# B.net
KiCad netlist of a schematic drawn in Altium Designer
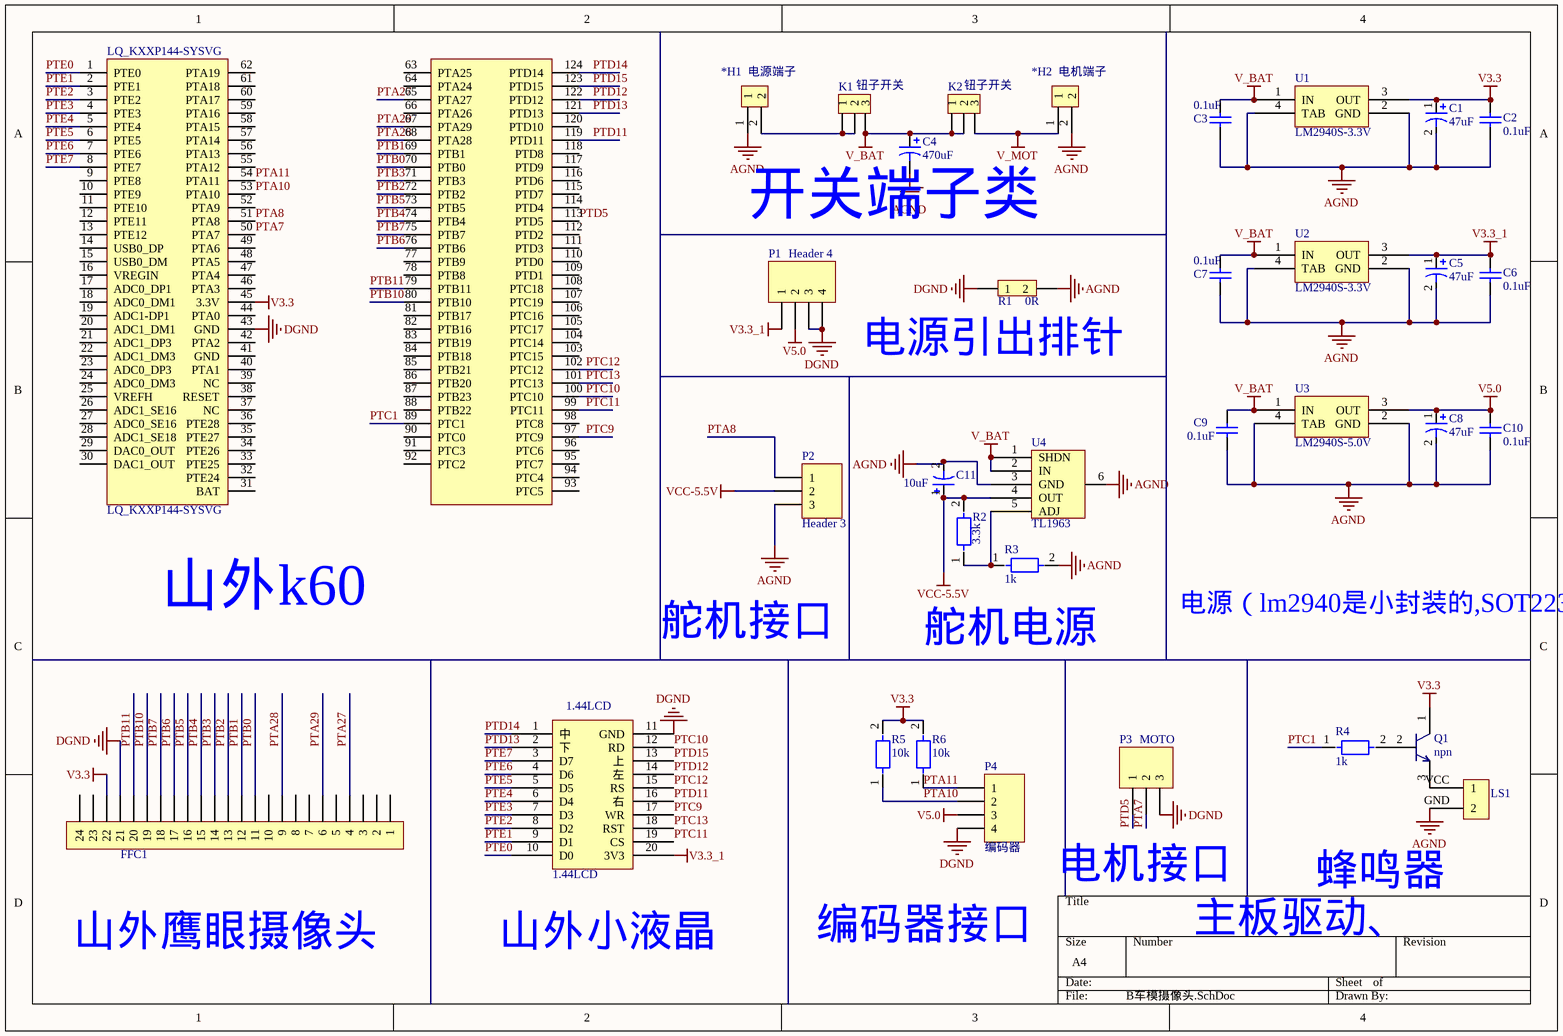
[diagram p0: B车模摄像头.SchDoc]

(export (version "E")
  (design (tool "Eeschema 10.0.6"))
  (components
    (comp (ref "*H1") (value "电源端子") (footprint "端子") (libsource (lib "Integrated_Library") (part "端子5MM")))
    (comp (ref "*H2") (value "电机端子") (footprint "端子") (libsource (lib "Integrated_Library") (part "端子5MM")))
    (comp (ref "1.44LCD")
      (value "1.44LCD")
      (footprint "1.44LCD")
      (libsource (lib "1.44LCD") (part "1.44LCD"))
    )
    (comp (ref "C1") (value "47uF") (footprint "3216") (libsource (lib "MOTOR") (part "CAP-TAN-47uF")))
    (comp (ref "C2") (value "0.1uF") (footprint "0805") (libsource (lib "MOTOR") (part "CAP-0805_1")))
    (comp (ref "C3") (value "0.1uF") (footprint "0805") (libsource (lib "MOTOR") (part "CAP-0805_1")))
    (comp (ref "C4")
      (value "470uF")
      (footprint "470UF")
      (description "Polarized Capacitor (Radial)")
      (fields (field (name "Comment") "Cap Pol1") (field (name "PUBLISHER") "Altium Limited"))
      (libsource (lib "第十届摄像头主板工程") (part "Cap Pol1"))
    )
    (comp (ref "C5") (value "47uF") (footprint "3216") (libsource (lib "MOTOR") (part "CAP-TAN-47uF")))
    (comp (ref "C6") (value "0.1uF") (footprint "0805") (libsource (lib "MOTOR") (part "CAP-0805_1")))
    (comp (ref "C7") (value "0.1uF") (footprint "0805") (libsource (lib "MOTOR") (part "CAP-0805_1")))
    (comp (ref "C8") (value "47uF") (footprint "3216") (libsource (lib "MOTOR") (part "CAP-TAN-47uF")))
    (comp (ref "C9") (value "0.1uF") (footprint "0805") (libsource (lib "MOTOR") (part "CAP-0805_1")))
    (comp (ref "C10") (value "0.1uF") (footprint "0805") (libsource (lib "MOTOR") (part "CAP-0805_1")))
    (comp (ref "C11") (value "10uF") (footprint "3216") (libsource (lib "MOTOR") (part "CAP-TAN-10uF")))
    (comp (ref "FFC1")
      (value "FFC_0.5_24")
      (footprint "摄像头软排")
      (description "FFC")
      (libsource (lib "第十届摄像头主板工程") (part "FFC_0.5_24"))
    )
    (comp (ref "K1")
      (value "钮子开关")
      (footprint "钮子开关")
      (description "钮子开关102")
      (libsource (lib "Integrated_Library") (part "钮子开关"))
    )
    (comp (ref "K2")
      (value "钮子开关")
      (footprint "钮子开关")
      (description "钮子开关102")
      (libsource (lib "Integrated_Library") (part "钮子开关"))
    )
    (comp (ref "LQ_KXXP144-SYSVG")
      (value "LQ_KXXP144-SYSVG")
      (footprint "LQ_KXXP144-SYSVG")
      (libsource (lib "LQ_KXXP144-SYSVGSCH") (part "LQ_KXXP144-SYSVG"))
    )
    (comp (ref "LS1")
      (value "0905小型蜂鸣器")
      (footprint "0905小型蜂鸣器")
      (description "0905小蜂鸣器")
      (libsource (lib "Integrated_Library") (part "0905小型蜂鸣器"))
    )
    (comp (ref "P1")
      (value "Header 4")
      (footprint "HDR1X4")
      (description "Header, 4-Pin")
      (fields (field (name "PUBLISHER") "Altium Limited"))
      (libsource (lib "Miscellaneous Connectors") (part "Header 4"))
    )
    (comp (ref "P2")
      (value "Header 3")
      (footprint "HDR1X3")
      (description "Header, 3-Pin")
      (fields (field (name "PUBLISHER") "Altium Limited"))
      (libsource (lib "") (part "Header 3_1"))
    )
    (comp (ref "P3")
      (value "MOTO")
      (footprint "HDR1X3")
      (description "Header, 3-Pin")
      (fields (field (name "PUBLISHER") "Altium Limited"))
      (libsource (lib "Miscellaneous Connectors") (part "Header 3"))
    )
    (comp (ref "P4")
      (value "编码器")
      (footprint "HDR1X4")
      (description "Header, 4-Pin")
      (fields (field (name "PUBLISHER") "Altium Limited"))
      (libsource (lib "") (part "Header 4_1"))
    )
    (comp (ref "Q1") (value "npn") (footprint "npn") (libsource (lib "Integrated_Library") (part "npn")))
    (comp (ref "R1")
      (value "R-0603")
      (footprint "R-0603 - duplicate1")
      (fields (field (name "VAUL") "0R"))
      (libsource (lib "Integrated_Library") (part "R-0603"))
    )
    (comp (ref "R2") (value "3.3k") (footprint "0805") (libsource (lib "MOTOR") (part "RES-0805")))
    (comp (ref "R3") (value "1k") (footprint "0805") (libsource (lib "MOTOR") (part "RES-0805")))
    (comp (ref "R4") (value "1k") (footprint "0805") (libsource (lib "MOTOR") (part "RES-0805")))
    (comp (ref "R5") (value "10k") (footprint "0805") (libsource (lib "MOTOR") (part "RES-0805")))
    (comp (ref "R6") (value "10k") (footprint "0805") (libsource (lib "MOTOR") (part "RES-0805")))
    (comp (ref "U1")
      (value "LM2940S-3.3V")
      (footprint "LM2940S-5.0")
      (libsource (lib "MOTOR") (part "LM2940S-5.0"))
    )
    (comp (ref "U2")
      (value "LM2940S-3.3V")
      (footprint "LM2940S-5.0")
      (libsource (lib "MOTOR") (part "LM2940S-5.0"))
    )
    (comp (ref "U3")
      (value "LM2940S-5.0V")
      (footprint "LM2940S-5.0")
      (libsource (lib "MOTOR") (part "LM2940S-5.0"))
    )
    (comp (ref "U4") (value "TL1963") (footprint "SOT223-5") (libsource (lib "第十届摄像头主板工程") (part "TL1963")))
  )
  (nets
    (net (code "1") (name "/PTA7") (class "Default")
      (node (ref "LQ_KXXP144-SYSVG") (pin "50") (pinfunction "PTA7_50") (pintype "passive"))
      (node (ref "P3") (pin "2") (pinfunction "2_2") (pintype "passive"))
    )
    (net (code "2") (name "/PTA8") (class "Default")
      (node (ref "LQ_KXXP144-SYSVG") (pin "51") (pinfunction "PTA8_51") (pintype "passive"))
      (node (ref "P2") (pin "1") (pinfunction "1_1") (pintype "passive"))
    )
    (net (code "3") (name "/PTA10") (class "Default")
      (node (ref "LQ_KXXP144-SYSVG") (pin "53") (pinfunction "PTA10_53") (pintype "passive"))
      (node (ref "P4") (pin "2") (pinfunction "2_2") (pintype "passive"))
      (node (ref "R5") (pin "1") (pinfunction "1_1") (pintype "passive"))
    )
    (net (code "4") (name "/PTA11") (class "Default")
      (node (ref "LQ_KXXP144-SYSVG") (pin "54") (pinfunction "PTA11_54") (pintype "passive"))
      (node (ref "P4") (pin "1") (pinfunction "1_1") (pintype "passive"))
      (node (ref "R6") (pin "1") (pinfunction "1_1") (pintype "passive"))
    )
    (net (code "5") (name "/PTA27") (class "Default")
      (node (ref "FFC1") (pin "4") (pinfunction "4_4") (pintype "passive"))
      (node (ref "LQ_KXXP144-SYSVG") (pin "65") (pinfunction "PTA27_65") (pintype "passive"))
    )
    (net (code "6") (name "/PTA28") (class "Default")
      (node (ref "FFC1") (pin "9") (pinfunction "9_9") (pintype "passive"))
      (node (ref "LQ_KXXP144-SYSVG") (pin "68") (pinfunction "PTA28_68") (pintype "passive"))
    )
    (net (code "7") (name "/PTA29") (class "Default")
      (node (ref "FFC1") (pin "6") (pinfunction "6_6") (pintype "passive"))
      (node (ref "LQ_KXXP144-SYSVG") (pin "67") (pinfunction "PTA29_67") (pintype "passive"))
    )
    (net (code "8") (name "/PTB0") (class "Default")
      (node (ref "FFC1") (pin "11") (pinfunction "11_11") (pintype "passive"))
      (node (ref "LQ_KXXP144-SYSVG") (pin "70") (pinfunction "PTB0_70") (pintype "passive"))
    )
    (net (code "9") (name "/PTB1") (class "Default")
      (node (ref "FFC1") (pin "12") (pinfunction "12_12") (pintype "passive"))
      (node (ref "LQ_KXXP144-SYSVG") (pin "69") (pinfunction "PTB1_69") (pintype "passive"))
    )
    (net (code "10") (name "/PTB2") (class "Default")
      (node (ref "FFC1") (pin "13") (pinfunction "13_13") (pintype "passive"))
      (node (ref "LQ_KXXP144-SYSVG") (pin "72") (pinfunction "PTB2_72") (pintype "passive"))
    )
    (net (code "11") (name "/PTB3") (class "Default")
      (node (ref "FFC1") (pin "14") (pinfunction "14_14") (pintype "passive"))
      (node (ref "LQ_KXXP144-SYSVG") (pin "71") (pinfunction "PTB3_71") (pintype "passive"))
    )
    (net (code "12") (name "/PTB4") (class "Default")
      (node (ref "FFC1") (pin "15") (pinfunction "15_15") (pintype "passive"))
      (node (ref "LQ_KXXP144-SYSVG") (pin "74") (pinfunction "PTB4_74") (pintype "passive"))
    )
    (net (code "13") (name "/PTB5") (class "Default")
      (node (ref "FFC1") (pin "16") (pinfunction "16_16") (pintype "passive"))
      (node (ref "LQ_KXXP144-SYSVG") (pin "73") (pinfunction "PTB5_73") (pintype "passive"))
    )
    (net (code "14") (name "/PTB6") (class "Default")
      (node (ref "FFC1") (pin "17") (pinfunction "17_17") (pintype "passive"))
      (node (ref "LQ_KXXP144-SYSVG") (pin "76") (pinfunction "PTB6_76") (pintype "passive"))
    )
    (net (code "15") (name "/PTB7") (class "Default")
      (node (ref "FFC1") (pin "18") (pinfunction "18_18") (pintype "passive"))
      (node (ref "LQ_KXXP144-SYSVG") (pin "75") (pinfunction "PTB7_75") (pintype "passive"))
    )
    (net (code "16") (name "/PTB10") (class "Default")
      (node (ref "FFC1") (pin "19") (pinfunction "19_19") (pintype "passive"))
      (node (ref "LQ_KXXP144-SYSVG") (pin "80") (pinfunction "PTB10_80") (pintype "passive"))
    )
    (net (code "17") (name "/PTB11") (class "Default")
      (node (ref "FFC1") (pin "20") (pinfunction "20_20") (pintype "passive"))
      (node (ref "LQ_KXXP144-SYSVG") (pin "79") (pinfunction "PTB11_79") (pintype "passive"))
    )
    (net (code "18") (name "/PTC1") (class "Default")
      (node (ref "LQ_KXXP144-SYSVG") (pin "89") (pinfunction "PTC1_89") (pintype "passive"))
      (node (ref "R4") (pin "1") (pinfunction "1_1") (pintype "passive"))
    )
    (net (code "19") (name "/PTC9") (class "Default")
      (node (ref "1.44LCD") (pin "17") (pinfunction "WR_17") (pintype "passive"))
      (node (ref "LQ_KXXP144-SYSVG") (pin "97") (pinfunction "PTC9_97") (pintype "passive"))
    )
    (net (code "20") (name "/PTC10") (class "Default")
      (node (ref "1.44LCD") (pin "12") (pinfunction "RD_12") (pintype "passive"))
      (node (ref "LQ_KXXP144-SYSVG") (pin "100") (pinfunction "PTC10_100") (pintype "passive"))
    )
    (net (code "21") (name "/PTC11") (class "Default")
      (node (ref "1.44LCD") (pin "19") (pinfunction "CS_19") (pintype "passive"))
      (node (ref "LQ_KXXP144-SYSVG") (pin "99") (pinfunction "PTC11_99") (pintype "passive"))
    )
    (net (code "22") (name "/PTC12") (class "Default")
      (node (ref "1.44LCD") (pin "15") (pinfunction "RS_15") (pintype "passive"))
      (node (ref "LQ_KXXP144-SYSVG") (pin "102") (pinfunction "PTC12_102") (pintype "passive"))
    )
    (net (code "23") (name "/PTC13") (class "Default")
      (node (ref "1.44LCD") (pin "18") (pinfunction "RST_18") (pintype "passive"))
      (node (ref "LQ_KXXP144-SYSVG") (pin "101") (pinfunction "PTC13_101") (pintype "passive"))
    )
    (net (code "24") (name "/PTD5") (class "Default")
      (node (ref "LQ_KXXP144-SYSVG") (pin "113") (pinfunction "PTD5_113") (pintype "passive"))
      (node (ref "P3") (pin "1") (pinfunction "1_1") (pintype "passive"))
    )
    (net (code "25") (name "/PTD11") (class "Default")
      (node (ref "1.44LCD") (pin "16") (pinfunction "右_16") (pintype "passive"))
      (node (ref "LQ_KXXP144-SYSVG") (pin "119") (pinfunction "PTD11_119") (pintype "passive"))
    )
    (net (code "26") (name "/PTD12") (class "Default")
      (node (ref "1.44LCD") (pin "14") (pinfunction "左_14") (pintype "passive"))
      (node (ref "LQ_KXXP144-SYSVG") (pin "122") (pinfunction "PTD12_122") (pintype "passive"))
    )
    (net (code "27") (name "/PTD13") (class "Default")
      (node (ref "1.44LCD") (pin "2") (pinfunction "下_2") (pintype "passive"))
      (node (ref "LQ_KXXP144-SYSVG") (pin "121") (pinfunction "PTD13_121") (pintype "passive"))
    )
    (net (code "28") (name "/PTD14") (class "Default")
      (node (ref "1.44LCD") (pin "1") (pinfunction "中_1") (pintype "passive"))
      (node (ref "LQ_KXXP144-SYSVG") (pin "124") (pinfunction "PTD14_124") (pintype "passive"))
    )
    (net (code "29") (name "/PTD15") (class "Default")
      (node (ref "1.44LCD") (pin "13") (pinfunction "上_13") (pintype "passive"))
      (node (ref "LQ_KXXP144-SYSVG") (pin "123") (pinfunction "PTD15_123") (pintype "passive"))
    )
    (net (code "30") (name "/PTE0") (class "Default")
      (node (ref "1.44LCD") (pin "10") (pinfunction "D0_10") (pintype "passive"))
      (node (ref "LQ_KXXP144-SYSVG") (pin "1") (pinfunction "PTE0_1") (pintype "passive"))
    )
    (net (code "31") (name "/PTE1") (class "Default")
      (node (ref "1.44LCD") (pin "9") (pinfunction "D1_9") (pintype "passive"))
      (node (ref "LQ_KXXP144-SYSVG") (pin "2") (pinfunction "PTE1_2") (pintype "passive"))
    )
    (net (code "32") (name "/PTE2") (class "Default")
      (node (ref "1.44LCD") (pin "8") (pinfunction "D2_8") (pintype "passive"))
      (node (ref "LQ_KXXP144-SYSVG") (pin "3") (pinfunction "PTE2_3") (pintype "passive"))
    )
    (net (code "33") (name "/PTE3") (class "Default")
      (node (ref "1.44LCD") (pin "7") (pinfunction "D3_7") (pintype "passive"))
      (node (ref "LQ_KXXP144-SYSVG") (pin "4") (pinfunction "PTE3_4") (pintype "passive"))
    )
    (net (code "34") (name "/PTE4") (class "Default")
      (node (ref "1.44LCD") (pin "6") (pinfunction "D4_6") (pintype "passive"))
      (node (ref "LQ_KXXP144-SYSVG") (pin "5") (pinfunction "PTE4_5") (pintype "passive"))
    )
    (net (code "35") (name "/PTE5") (class "Default")
      (node (ref "1.44LCD") (pin "5") (pinfunction "D5_5") (pintype "passive"))
      (node (ref "LQ_KXXP144-SYSVG") (pin "6") (pinfunction "PTE5_6") (pintype "passive"))
    )
    (net (code "36") (name "/PTE6") (class "Default")
      (node (ref "1.44LCD") (pin "4") (pinfunction "D6_4") (pintype "passive"))
      (node (ref "LQ_KXXP144-SYSVG") (pin "7") (pinfunction "PTE6_7") (pintype "passive"))
    )
    (net (code "37") (name "/PTE7") (class "Default")
      (node (ref "1.44LCD") (pin "3") (pinfunction "D7_3") (pintype "passive"))
      (node (ref "LQ_KXXP144-SYSVG") (pin "8") (pinfunction "PTE7_8") (pintype "passive"))
    )
    (net (code "50") (name "AGND") (class "Default")
      (node (ref "*H1") (pin "1") (pinfunction "1_1") (pintype "passive"))
      (node (ref "*H2") (pin "2") (pinfunction "2_2") (pintype "passive"))
      (node (ref "C1") (pin "2") (pinfunction "2_2") (pintype "passive"))
      (node (ref "C10") (pin "2") (pinfunction "2_2") (pintype "passive"))
      (node (ref "C11") (pin "2") (pinfunction "2_2") (pintype "passive"))
      (node (ref "C2") (pin "2") (pinfunction "2_2") (pintype "passive"))
      (node (ref "C3") (pin "2") (pinfunction "2_2") (pintype "passive"))
      (node (ref "C4") (pin "2") (pinfunction "2_2") (pintype "passive"))
      (node (ref "C5") (pin "2") (pinfunction "2_2") (pintype "passive"))
      (node (ref "C6") (pin "2") (pinfunction "2_2") (pintype "passive"))
      (node (ref "C7") (pin "2") (pinfunction "2_2") (pintype "passive"))
      (node (ref "C8") (pin "2") (pinfunction "2_2") (pintype "passive"))
      (node (ref "C9") (pin "2") (pinfunction "2_2") (pintype "passive"))
      (node (ref "LS1") (pin "GND") (pinfunction "2_GND") (pintype "passive"))
      (node (ref "P2") (pin "3") (pinfunction "3_3") (pintype "passive"))
      (node (ref "R1") (pin "3") (pinfunction "2_3") (pintype "passive"))
      (node (ref "R3") (pin "2") (pinfunction "2_2") (pintype "passive"))
      (node (ref "U1") (pin "2") (pinfunction "GND_2") (pintype "passive"))
      (node (ref "U1") (pin "4") (pinfunction "TAB_4") (pintype "passive"))
      (node (ref "U2") (pin "2") (pinfunction "GND_2") (pintype "passive"))
      (node (ref "U2") (pin "4") (pinfunction "TAB_4") (pintype "passive"))
      (node (ref "U3") (pin "2") (pinfunction "GND_2") (pintype "passive"))
      (node (ref "U3") (pin "4") (pinfunction "TAB_4") (pintype "passive"))
      (node (ref "U4") (pin "3") (pinfunction "GND_3") (pintype "passive"))
      (node (ref "U4") (pin "6") (pinfunction "GND_6") (pintype "passive"))
    )
    (net (code "51") (name "DGND") (class "Default")
      (node (ref "1.44LCD") (pin "11") (pinfunction "GND_11") (pintype "passive"))
      (node (ref "FFC1") (pin "21") (pinfunction "21_21") (pintype "passive"))
      (node (ref "LQ_KXXP144-SYSVG") (pin "43") (pinfunction "GND_43") (pintype "passive"))
      (node (ref "P1") (pin "3") (pinfunction "3_3") (pintype "passive"))
      (node (ref "P1") (pin "4") (pinfunction "4_4") (pintype "passive"))
      (node (ref "P3") (pin "3") (pinfunction "3_3") (pintype "passive"))
      (node (ref "P4") (pin "4") (pinfunction "4_4") (pintype "passive"))
      (node (ref "R1") (pin "2") (pinfunction "1_2") (pintype "passive"))
    )
    (net (code "52") (name "Net-(*H1-Pad2)") (class "Default")
      (node (ref "*H1") (pin "2") (pinfunction "2_2") (pintype "passive"))
      (node (ref "K1") (pin "1") (pinfunction "1_1") (pintype "passive"))
      (node (ref "K1") (pin "2") (pinfunction "2_2") (pintype "passive"))
    )
    (net (code "53") (name "Net-(LS1-1)") (class "Default")
      (node (ref "LS1") (pin "VCC") (pinfunction "1_VCC") (pintype "passive"))
      (node (ref "Q1") (pin "3") (pinfunction "3_3") (pintype "passive"))
    )
    (net (code "54") (name "Net-(Q1-Pad2)") (class "Default")
      (node (ref "Q1") (pin "2") (pinfunction "2_2") (pintype "passive"))
      (node (ref "R4") (pin "2") (pinfunction "2_2") (pintype "passive"))
    )
    (net (code "55") (name "Net-(U4-ADJ)") (class "Default")
      (node (ref "R2") (pin "1") (pinfunction "1_1") (pintype "passive"))
      (node (ref "R3") (pin "1") (pinfunction "1_1") (pintype "passive"))
      (node (ref "U4") (pin "5") (pinfunction "ADJ_5") (pintype "passive"))
    )
    (net (code "56") (name "V3.3") (class "Default")
      (node (ref "C1") (pin "1") (pinfunction "1_1") (pintype "passive"))
      (node (ref "C2") (pin "1") (pinfunction "1_1") (pintype "passive"))
      (node (ref "FFC1") (pin "22") (pinfunction "22_22") (pintype "passive"))
      (node (ref "LQ_KXXP144-SYSVG") (pin "45") (pinfunction "3.3V_45") (pintype "passive"))
      (node (ref "Q1") (pin "1") (pinfunction "1_1") (pintype "passive"))
      (node (ref "R5") (pin "2") (pinfunction "2_2") (pintype "passive"))
      (node (ref "R6") (pin "2") (pinfunction "2_2") (pintype "passive"))
      (node (ref "U1") (pin "3") (pinfunction "OUT_3") (pintype "passive"))
    )
    (net (code "57") (name "V3.3_1") (class "Default")
      (node (ref "1.44LCD") (pin "20") (pinfunction "3V3_20") (pintype "passive"))
      (node (ref "C5") (pin "1") (pinfunction "1_1") (pintype "passive"))
      (node (ref "C6") (pin "1") (pinfunction "1_1") (pintype "passive"))
      (node (ref "P1") (pin "1") (pinfunction "1_1") (pintype "passive"))
      (node (ref "U2") (pin "3") (pinfunction "OUT_3") (pintype "passive"))
    )
    (net (code "58") (name "V5.0") (class "Default")
      (node (ref "C10") (pin "1") (pinfunction "1_1") (pintype "passive"))
      (node (ref "C8") (pin "1") (pinfunction "1_1") (pintype "passive"))
      (node (ref "P1") (pin "2") (pinfunction "2_2") (pintype "passive"))
      (node (ref "P4") (pin "3") (pinfunction "3_3") (pintype "passive"))
      (node (ref "U3") (pin "3") (pinfunction "OUT_3") (pintype "passive"))
    )
    (net (code "59") (name "VCC-5.5V") (class "Default")
      (node (ref "C11") (pin "1") (pinfunction "1_1") (pintype "passive"))
      (node (ref "P2") (pin "2") (pinfunction "2_2") (pintype "passive"))
      (node (ref "R2") (pin "2") (pinfunction "2_2") (pintype "passive"))
      (node (ref "U4") (pin "4") (pinfunction "OUT_4") (pintype "passive"))
    )
    (net (code "60") (name "V_BAT") (class "Default")
      (node (ref "C3") (pin "1") (pinfunction "1_1") (pintype "passive"))
      (node (ref "C4") (pin "1") (pinfunction "1_1") (pintype "passive"))
      (node (ref "C7") (pin "1") (pinfunction "1_1") (pintype "passive"))
      (node (ref "C9") (pin "1") (pinfunction "1_1") (pintype "passive"))
      (node (ref "K1") (pin "3") (pinfunction "3_3") (pintype "passive"))
      (node (ref "K2") (pin "1") (pinfunction "1_1") (pintype "passive"))
      (node (ref "K2") (pin "2") (pinfunction "2_2") (pintype "passive"))
      (node (ref "U1") (pin "1") (pinfunction "IN_1") (pintype "passive"))
      (node (ref "U2") (pin "1") (pinfunction "IN_1") (pintype "passive"))
      (node (ref "U3") (pin "1") (pinfunction "IN_1") (pintype "passive"))
      (node (ref "U4") (pin "1") (pinfunction "SHDN_1") (pintype "passive"))
      (node (ref "U4") (pin "2") (pinfunction "IN_2") (pintype "passive"))
    )
    (net (code "61") (name "V_MOT") (class "Default")
      (node (ref "*H2") (pin "1") (pinfunction "1_1") (pintype "passive"))
      (node (ref "K2") (pin "3") (pinfunction "3_3") (pintype "passive"))
    )
    (net (code "62") (name "unconnected-(FFC1-Pad1)") (class "Default")
      (node (ref "FFC1") (pin "1") (pinfunction "1_1") (pintype "passive"))
    )
    (net (code "63") (name "unconnected-(FFC1-Pad2)") (class "Default")
      (node (ref "FFC1") (pin "2") (pinfunction "2_2") (pintype "passive"))
    )
    (net (code "64") (name "unconnected-(FFC1-Pad3)") (class "Default")
      (node (ref "FFC1") (pin "3") (pinfunction "3_3") (pintype "passive"))
    )
    (net (code "65") (name "unconnected-(FFC1-Pad5)") (class "Default")
      (node (ref "FFC1") (pin "5") (pinfunction "5_5") (pintype "passive"))
    )
    (net (code "66") (name "unconnected-(FFC1-Pad7)") (class "Default")
      (node (ref "FFC1") (pin "7") (pinfunction "7_7") (pintype "passive"))
    )
    (net (code "67") (name "unconnected-(FFC1-Pad8)") (class "Default")
      (node (ref "FFC1") (pin "8") (pinfunction "8_8") (pintype "passive"))
    )
    (net (code "68") (name "unconnected-(FFC1-Pad10)") (class "Default")
      (node (ref "FFC1") (pin "10") (pinfunction "10_10") (pintype "passive"))
    )
    (net (code "69") (name "unconnected-(FFC1-Pad23)") (class "Default")
      (node (ref "FFC1") (pin "23") (pinfunction "23_23") (pintype "passive"))
    )
    (net (code "70") (name "unconnected-(FFC1-Pad24)") (class "Default")
      (node (ref "FFC1") (pin "24") (pinfunction "24_24") (pintype "passive"))
    )
    (net (code "71") (name "unconnected-(LQ_KXXP144-SYSVG-ADC0_DM1-Pad18)") (class "Default")
      (node (ref "LQ_KXXP144-SYSVG") (pin "18") (pinfunction "ADC0_DM1_18") (pintype "passive"))
    )
    (net (code "72") (name "unconnected-(LQ_KXXP144-SYSVG-ADC0_DM3-Pad24)") (class "Default")
      (node (ref "LQ_KXXP144-SYSVG") (pin "24") (pinfunction "ADC0_DM3_24") (pintype "passive"))
    )
    (net (code "73") (name "unconnected-(LQ_KXXP144-SYSVG-ADC0_DP1-Pad17)") (class "Default")
      (node (ref "LQ_KXXP144-SYSVG") (pin "17") (pinfunction "ADC0_DP1_17") (pintype "passive"))
    )
    (net (code "74") (name "unconnected-(LQ_KXXP144-SYSVG-ADC0_DP3-Pad23)") (class "Default")
      (node (ref "LQ_KXXP144-SYSVG") (pin "23") (pinfunction "ADC0_DP3_23") (pintype "passive"))
    )
    (net (code "75") (name "unconnected-(LQ_KXXP144-SYSVG-ADC0_SE16-Pad27)") (class "Default")
      (node (ref "LQ_KXXP144-SYSVG") (pin "27") (pinfunction "ADC0_SE16_27") (pintype "passive"))
    )
    (net (code "76") (name "unconnected-(LQ_KXXP144-SYSVG-ADC1-DP1-Pad19)") (class "Default")
      (node (ref "LQ_KXXP144-SYSVG") (pin "19") (pinfunction "ADC1-DP1_19") (pintype "passive"))
    )
    (net (code "77") (name "unconnected-(LQ_KXXP144-SYSVG-ADC1_DM1-Pad20)") (class "Default")
      (node (ref "LQ_KXXP144-SYSVG") (pin "20") (pinfunction "ADC1_DM1_20") (pintype "passive"))
    )
    (net (code "78") (name "unconnected-(LQ_KXXP144-SYSVG-ADC1_DM3-Pad22)") (class "Default")
      (node (ref "LQ_KXXP144-SYSVG") (pin "22") (pinfunction "ADC1_DM3_22") (pintype "passive"))
    )
    (net (code "79") (name "unconnected-(LQ_KXXP144-SYSVG-ADC1_DP3-Pad21)") (class "Default")
      (node (ref "LQ_KXXP144-SYSVG") (pin "21") (pinfunction "ADC1_DP3_21") (pintype "passive"))
    )
    (net (code "80") (name "unconnected-(LQ_KXXP144-SYSVG-ADC1_SE16-Pad26)") (class "Default")
      (node (ref "LQ_KXXP144-SYSVG") (pin "26") (pinfunction "ADC1_SE16_26") (pintype "passive"))
    )
    (net (code "81") (name "unconnected-(LQ_KXXP144-SYSVG-ADC1_SE18-Pad28)") (class "Default")
      (node (ref "LQ_KXXP144-SYSVG") (pin "28") (pinfunction "ADC1_SE18_28") (pintype "passive"))
    )
    (net (code "82") (name "unconnected-(LQ_KXXP144-SYSVG-BAT-Pad31)") (class "Default")
      (node (ref "LQ_KXXP144-SYSVG") (pin "31") (pinfunction "BAT_31") (pintype "passive"))
    )
    (net (code "83") (name "unconnected-(LQ_KXXP144-SYSVG-DAC0_OUT-Pad29)") (class "Default")
      (node (ref "LQ_KXXP144-SYSVG") (pin "29") (pinfunction "DAC0_OUT_29") (pintype "passive"))
    )
    (net (code "84") (name "unconnected-(LQ_KXXP144-SYSVG-DAC1_OUT-Pad30)") (class "Default")
      (node (ref "LQ_KXXP144-SYSVG") (pin "30") (pinfunction "DAC1_OUT_30") (pintype "passive"))
    )
    (net (code "85") (name "unconnected-(LQ_KXXP144-SYSVG-GND-Pad41)") (class "Default")
      (node (ref "LQ_KXXP144-SYSVG") (pin "41") (pinfunction "GND_41") (pintype "passive"))
    )
    (net (code "86") (name "unconnected-(LQ_KXXP144-SYSVG-NC-Pad37)") (class "Default")
      (node (ref "LQ_KXXP144-SYSVG") (pin "37") (pinfunction "NC_37") (pintype "passive"))
    )
    (net (code "87") (name "unconnected-(LQ_KXXP144-SYSVG-NC-Pad39)") (class "Default")
      (node (ref "LQ_KXXP144-SYSVG") (pin "39") (pinfunction "NC_39") (pintype "passive"))
    )
    (net (code "88") (name "unconnected-(LQ_KXXP144-SYSVG-PTA0-Pad44)") (class "Default")
      (node (ref "LQ_KXXP144-SYSVG") (pin "44") (pinfunction "PTA0_44") (pintype "passive"))
    )
    (net (code "89") (name "unconnected-(LQ_KXXP144-SYSVG-PTA1-Pad40)") (class "Default")
      (node (ref "LQ_KXXP144-SYSVG") (pin "40") (pinfunction "PTA1_40") (pintype "passive"))
    )
    (net (code "90") (name "unconnected-(LQ_KXXP144-SYSVG-PTA2-Pad42)") (class "Default")
      (node (ref "LQ_KXXP144-SYSVG") (pin "42") (pinfunction "PTA2_42") (pintype "passive"))
    )
    (net (code "91") (name "unconnected-(LQ_KXXP144-SYSVG-PTA3-Pad46)") (class "Default")
      (node (ref "LQ_KXXP144-SYSVG") (pin "46") (pinfunction "PTA3_46") (pintype "passive"))
    )
    (net (code "92") (name "unconnected-(LQ_KXXP144-SYSVG-PTA4-Pad47)") (class "Default")
      (node (ref "LQ_KXXP144-SYSVG") (pin "47") (pinfunction "PTA4_47") (pintype "passive"))
    )
    (net (code "93") (name "unconnected-(LQ_KXXP144-SYSVG-PTA5-Pad48)") (class "Default")
      (node (ref "LQ_KXXP144-SYSVG") (pin "48") (pinfunction "PTA5_48") (pintype "passive"))
    )
    (net (code "94") (name "unconnected-(LQ_KXXP144-SYSVG-PTA6-Pad49)") (class "Default")
      (node (ref "LQ_KXXP144-SYSVG") (pin "49") (pinfunction "PTA6_49") (pintype "passive"))
    )
    (net (code "95") (name "unconnected-(LQ_KXXP144-SYSVG-PTA9-Pad52)") (class "Default")
      (node (ref "LQ_KXXP144-SYSVG") (pin "52") (pinfunction "PTA9_52") (pintype "passive"))
    )
    (net (code "96") (name "unconnected-(LQ_KXXP144-SYSVG-PTA12-Pad55)") (class "Default")
      (node (ref "LQ_KXXP144-SYSVG") (pin "55") (pinfunction "PTA12_55") (pintype "passive"))
    )
    (net (code "97") (name "unconnected-(LQ_KXXP144-SYSVG-PTA13-Pad56)") (class "Default")
      (node (ref "LQ_KXXP144-SYSVG") (pin "56") (pinfunction "PTA13_56") (pintype "passive"))
    )
    (net (code "98") (name "unconnected-(LQ_KXXP144-SYSVG-PTA14-Pad57)") (class "Default")
      (node (ref "LQ_KXXP144-SYSVG") (pin "57") (pinfunction "PTA14_57") (pintype "passive"))
    )
    (net (code "99") (name "unconnected-(LQ_KXXP144-SYSVG-PTA15-Pad58)") (class "Default")
      (node (ref "LQ_KXXP144-SYSVG") (pin "58") (pinfunction "PTA15_58") (pintype "passive"))
    )
    (net (code "100") (name "unconnected-(LQ_KXXP144-SYSVG-PTA16-Pad59)") (class "Default")
      (node (ref "LQ_KXXP144-SYSVG") (pin "59") (pinfunction "PTA16_59") (pintype "passive"))
    )
    (net (code "101") (name "unconnected-(LQ_KXXP144-SYSVG-PTA17-Pad60)") (class "Default")
      (node (ref "LQ_KXXP144-SYSVG") (pin "60") (pinfunction "PTA17_60") (pintype "passive"))
    )
    (net (code "102") (name "unconnected-(LQ_KXXP144-SYSVG-PTA18-Pad61)") (class "Default")
      (node (ref "LQ_KXXP144-SYSVG") (pin "61") (pinfunction "PTA18_61") (pintype "passive"))
    )
    (net (code "103") (name "unconnected-(LQ_KXXP144-SYSVG-PTA19-Pad62)") (class "Default")
      (node (ref "LQ_KXXP144-SYSVG") (pin "62") (pinfunction "PTA19_62") (pintype "passive"))
    )
    (net (code "104") (name "unconnected-(LQ_KXXP144-SYSVG-PTA24-Pad64)") (class "Default")
      (node (ref "LQ_KXXP144-SYSVG") (pin "64") (pinfunction "PTA24_64") (pintype "passive"))
    )
    (net (code "105") (name "unconnected-(LQ_KXXP144-SYSVG-PTA25-Pad63)") (class "Default")
      (node (ref "LQ_KXXP144-SYSVG") (pin "63") (pinfunction "PTA25_63") (pintype "passive"))
    )
    (net (code "106") (name "unconnected-(LQ_KXXP144-SYSVG-PTA26-Pad66)") (class "Default")
      (node (ref "LQ_KXXP144-SYSVG") (pin "66") (pinfunction "PTA26_66") (pintype "passive"))
    )
    (net (code "107") (name "unconnected-(LQ_KXXP144-SYSVG-PTB8-Pad78)") (class "Default")
      (node (ref "LQ_KXXP144-SYSVG") (pin "78") (pinfunction "PTB8_78") (pintype "passive"))
    )
    (net (code "108") (name "unconnected-(LQ_KXXP144-SYSVG-PTB9-Pad77)") (class "Default")
      (node (ref "LQ_KXXP144-SYSVG") (pin "77") (pinfunction "PTB9_77") (pintype "passive"))
    )
    (net (code "109") (name "unconnected-(LQ_KXXP144-SYSVG-PTB16-Pad82)") (class "Default")
      (node (ref "LQ_KXXP144-SYSVG") (pin "82") (pinfunction "PTB16_82") (pintype "passive"))
    )
    (net (code "110") (name "unconnected-(LQ_KXXP144-SYSVG-PTB17-Pad81)") (class "Default")
      (node (ref "LQ_KXXP144-SYSVG") (pin "81") (pinfunction "PTB17_81") (pintype "passive"))
    )
    (net (code "111") (name "unconnected-(LQ_KXXP144-SYSVG-PTB18-Pad84)") (class "Default")
      (node (ref "LQ_KXXP144-SYSVG") (pin "84") (pinfunction "PTB18_84") (pintype "passive"))
    )
    (net (code "112") (name "unconnected-(LQ_KXXP144-SYSVG-PTB19-Pad83)") (class "Default")
      (node (ref "LQ_KXXP144-SYSVG") (pin "83") (pinfunction "PTB19_83") (pintype "passive"))
    )
    (net (code "113") (name "unconnected-(LQ_KXXP144-SYSVG-PTB20-Pad86)") (class "Default")
      (node (ref "LQ_KXXP144-SYSVG") (pin "86") (pinfunction "PTB20_86") (pintype "passive"))
    )
    (net (code "114") (name "unconnected-(LQ_KXXP144-SYSVG-PTB21-Pad85)") (class "Default")
      (node (ref "LQ_KXXP144-SYSVG") (pin "85") (pinfunction "PTB21_85") (pintype "passive"))
    )
    (net (code "115") (name "unconnected-(LQ_KXXP144-SYSVG-PTB22-Pad88)") (class "Default")
      (node (ref "LQ_KXXP144-SYSVG") (pin "88") (pinfunction "PTB22_88") (pintype "passive"))
    )
    (net (code "116") (name "unconnected-(LQ_KXXP144-SYSVG-PTB23-Pad87)") (class "Default")
      (node (ref "LQ_KXXP144-SYSVG") (pin "87") (pinfunction "PTB23_87") (pintype "passive"))
    )
    (net (code "117") (name "unconnected-(LQ_KXXP144-SYSVG-PTC0-Pad90)") (class "Default")
      (node (ref "LQ_KXXP144-SYSVG") (pin "90") (pinfunction "PTC0_90") (pintype "passive"))
    )
    (net (code "118") (name "unconnected-(LQ_KXXP144-SYSVG-PTC2-Pad92)") (class "Default")
      (node (ref "LQ_KXXP144-SYSVG") (pin "92") (pinfunction "PTC2_92") (pintype "passive"))
    )
    (net (code "119") (name "unconnected-(LQ_KXXP144-SYSVG-PTC3-Pad91)") (class "Default")
      (node (ref "LQ_KXXP144-SYSVG") (pin "91") (pinfunction "PTC3_91") (pintype "passive"))
    )
    (net (code "120") (name "unconnected-(LQ_KXXP144-SYSVG-PTC4-Pad94)") (class "Default")
      (node (ref "LQ_KXXP144-SYSVG") (pin "94") (pinfunction "PTC4_94") (pintype "passive"))
    )
    (net (code "121") (name "unconnected-(LQ_KXXP144-SYSVG-PTC5-Pad93)") (class "Default")
      (node (ref "LQ_KXXP144-SYSVG") (pin "93") (pinfunction "PTC5_93") (pintype "passive"))
    )
    (net (code "122") (name "unconnected-(LQ_KXXP144-SYSVG-PTC6-Pad96)") (class "Default")
      (node (ref "LQ_KXXP144-SYSVG") (pin "96") (pinfunction "PTC6_96") (pintype "passive"))
    )
    (net (code "123") (name "unconnected-(LQ_KXXP144-SYSVG-PTC7-Pad95)") (class "Default")
      (node (ref "LQ_KXXP144-SYSVG") (pin "95") (pinfunction "PTC7_95") (pintype "passive"))
    )
    (net (code "124") (name "unconnected-(LQ_KXXP144-SYSVG-PTC8-Pad98)") (class "Default")
      (node (ref "LQ_KXXP144-SYSVG") (pin "98") (pinfunction "PTC8_98") (pintype "passive"))
    )
    (net (code "125") (name "unconnected-(LQ_KXXP144-SYSVG-PTC14-Pad104)") (class "Default")
      (node (ref "LQ_KXXP144-SYSVG") (pin "104") (pinfunction "PTC14_104") (pintype "passive"))
    )
    (net (code "126") (name "unconnected-(LQ_KXXP144-SYSVG-PTC15-Pad103)") (class "Default")
      (node (ref "LQ_KXXP144-SYSVG") (pin "103") (pinfunction "PTC15_103") (pintype "passive"))
    )
    (net (code "127") (name "unconnected-(LQ_KXXP144-SYSVG-PTC16-Pad106)") (class "Default")
      (node (ref "LQ_KXXP144-SYSVG") (pin "106") (pinfunction "PTC16_106") (pintype "passive"))
    )
    (net (code "128") (name "unconnected-(LQ_KXXP144-SYSVG-PTC17-Pad105)") (class "Default")
      (node (ref "LQ_KXXP144-SYSVG") (pin "105") (pinfunction "PTC17_105") (pintype "passive"))
    )
    (net (code "129") (name "unconnected-(LQ_KXXP144-SYSVG-PTC18-Pad108)") (class "Default")
      (node (ref "LQ_KXXP144-SYSVG") (pin "108") (pinfunction "PTC18_108") (pintype "passive"))
    )
    (net (code "130") (name "unconnected-(LQ_KXXP144-SYSVG-PTC19-Pad107)") (class "Default")
      (node (ref "LQ_KXXP144-SYSVG") (pin "107") (pinfunction "PTC19_107") (pintype "passive"))
    )
    (net (code "131") (name "unconnected-(LQ_KXXP144-SYSVG-PTD0-Pad110)") (class "Default")
      (node (ref "LQ_KXXP144-SYSVG") (pin "110") (pinfunction "PTD0_110") (pintype "passive"))
    )
    (net (code "132") (name "unconnected-(LQ_KXXP144-SYSVG-PTD1-Pad109)") (class "Default")
      (node (ref "LQ_KXXP144-SYSVG") (pin "109") (pinfunction "PTD1_109") (pintype "passive"))
    )
    (net (code "133") (name "unconnected-(LQ_KXXP144-SYSVG-PTD2-Pad112)") (class "Default")
      (node (ref "LQ_KXXP144-SYSVG") (pin "112") (pinfunction "PTD2_112") (pintype "passive"))
    )
    (net (code "134") (name "unconnected-(LQ_KXXP144-SYSVG-PTD3-Pad111)") (class "Default")
      (node (ref "LQ_KXXP144-SYSVG") (pin "111") (pinfunction "PTD3_111") (pintype "passive"))
    )
    (net (code "135") (name "unconnected-(LQ_KXXP144-SYSVG-PTD4-Pad114)") (class "Default")
      (node (ref "LQ_KXXP144-SYSVG") (pin "114") (pinfunction "PTD4_114") (pintype "passive"))
    )
    (net (code "136") (name "unconnected-(LQ_KXXP144-SYSVG-PTD6-Pad116)") (class "Default")
      (node (ref "LQ_KXXP144-SYSVG") (pin "116") (pinfunction "PTD6_116") (pintype "passive"))
    )
    (net (code "137") (name "unconnected-(LQ_KXXP144-SYSVG-PTD7-Pad115)") (class "Default")
      (node (ref "LQ_KXXP144-SYSVG") (pin "115") (pinfunction "PTD7_115") (pintype "passive"))
    )
    (net (code "138") (name "unconnected-(LQ_KXXP144-SYSVG-PTD8-Pad118)") (class "Default")
      (node (ref "LQ_KXXP144-SYSVG") (pin "118") (pinfunction "PTD8_118") (pintype "passive"))
    )
    (net (code "139") (name "unconnected-(LQ_KXXP144-SYSVG-PTD9-Pad117)") (class "Default")
      (node (ref "LQ_KXXP144-SYSVG") (pin "117") (pinfunction "PTD9_117") (pintype "passive"))
    )
    (net (code "140") (name "unconnected-(LQ_KXXP144-SYSVG-PTD10-Pad120)") (class "Default")
      (node (ref "LQ_KXXP144-SYSVG") (pin "120") (pinfunction "PTD10_120") (pintype "passive"))
    )
    (net (code "141") (name "unconnected-(LQ_KXXP144-SYSVG-PTE8-Pad9)") (class "Default")
      (node (ref "LQ_KXXP144-SYSVG") (pin "9") (pinfunction "PTE8_9") (pintype "passive"))
    )
    (net (code "142") (name "unconnected-(LQ_KXXP144-SYSVG-PTE9-Pad10)") (class "Default")
      (node (ref "LQ_KXXP144-SYSVG") (pin "10") (pinfunction "PTE9_10") (pintype "passive"))
    )
    (net (code "143") (name "unconnected-(LQ_KXXP144-SYSVG-PTE10-Pad11)") (class "Default")
      (node (ref "LQ_KXXP144-SYSVG") (pin "11") (pinfunction "PTE10_11") (pintype "passive"))
    )
    (net (code "144") (name "unconnected-(LQ_KXXP144-SYSVG-PTE11-Pad12)") (class "Default")
      (node (ref "LQ_KXXP144-SYSVG") (pin "12") (pinfunction "PTE11_12") (pintype "passive"))
    )
    (net (code "145") (name "unconnected-(LQ_KXXP144-SYSVG-PTE12-Pad13)") (class "Default")
      (node (ref "LQ_KXXP144-SYSVG") (pin "13") (pinfunction "PTE12_13") (pintype "passive"))
    )
    (net (code "146") (name "unconnected-(LQ_KXXP144-SYSVG-PTE24-Pad32)") (class "Default")
      (node (ref "LQ_KXXP144-SYSVG") (pin "32") (pinfunction "PTE24_32") (pintype "passive"))
    )
    (net (code "147") (name "unconnected-(LQ_KXXP144-SYSVG-PTE25-Pad33)") (class "Default")
      (node (ref "LQ_KXXP144-SYSVG") (pin "33") (pinfunction "PTE25_33") (pintype "passive"))
    )
    (net (code "148") (name "unconnected-(LQ_KXXP144-SYSVG-PTE26-Pad34)") (class "Default")
      (node (ref "LQ_KXXP144-SYSVG") (pin "34") (pinfunction "PTE26_34") (pintype "passive"))
    )
    (net (code "149") (name "unconnected-(LQ_KXXP144-SYSVG-PTE27-Pad35)") (class "Default")
      (node (ref "LQ_KXXP144-SYSVG") (pin "35") (pinfunction "PTE27_35") (pintype "passive"))
    )
    (net (code "150") (name "unconnected-(LQ_KXXP144-SYSVG-PTE28-Pad36)") (class "Default")
      (node (ref "LQ_KXXP144-SYSVG") (pin "36") (pinfunction "PTE28_36") (pintype "passive"))
    )
    (net (code "151") (name "unconnected-(LQ_KXXP144-SYSVG-RESET-Pad38)") (class "Default")
      (node (ref "LQ_KXXP144-SYSVG") (pin "38") (pinfunction "RESET_38") (pintype "passive"))
    )
    (net (code "152") (name "unconnected-(LQ_KXXP144-SYSVG-USB0_DM-Pad15)") (class "Default")
      (node (ref "LQ_KXXP144-SYSVG") (pin "15") (pinfunction "USB0_DM_15") (pintype "passive"))
    )
    (net (code "153") (name "unconnected-(LQ_KXXP144-SYSVG-USB0_DP-Pad14)") (class "Default")
      (node (ref "LQ_KXXP144-SYSVG") (pin "14") (pinfunction "USB0_DP_14") (pintype "passive"))
    )
    (net (code "154") (name "unconnected-(LQ_KXXP144-SYSVG-VREFH-Pad25)") (class "Default")
      (node (ref "LQ_KXXP144-SYSVG") (pin "25") (pinfunction "VREFH_25") (pintype "passive"))
    )
    (net (code "155") (name "unconnected-(LQ_KXXP144-SYSVG-VREGIN-Pad16)") (class "Default")
      (node (ref "LQ_KXXP144-SYSVG") (pin "16") (pinfunction "VREGIN_16") (pintype "passive"))
    )
  )
)
